# MSSRP-Connectors.net
KiCad netlist of a schematic drawn in EAGLE
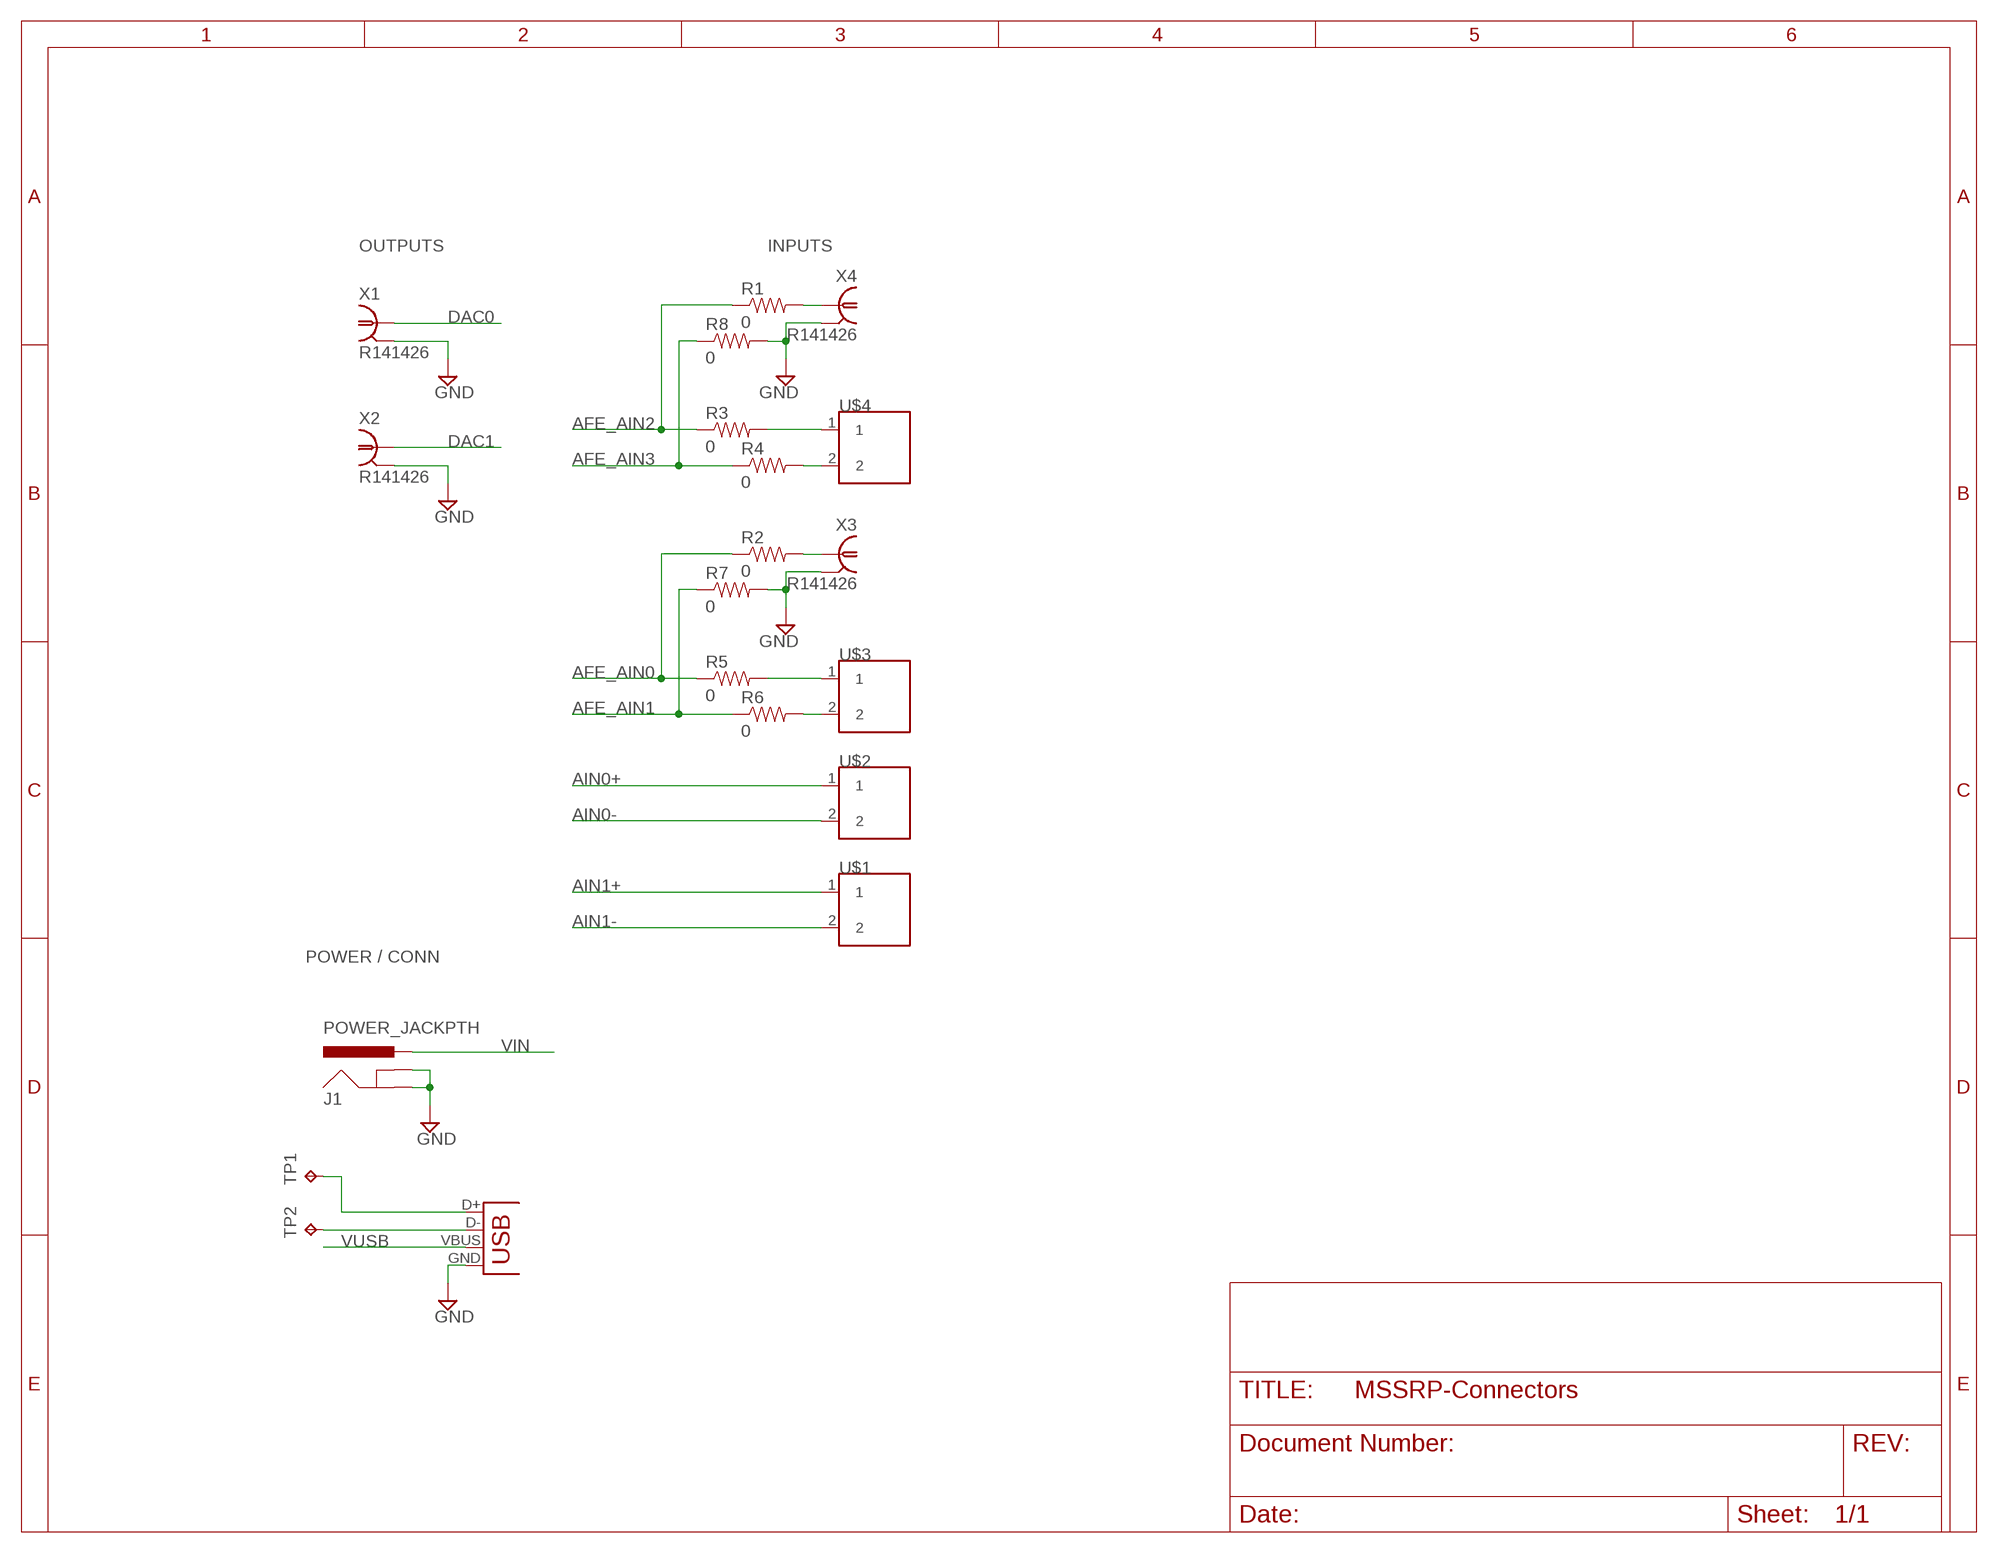
[diagram p0: schematic, sheet 1]

(export (version "E")
  (design (tool "Eeschema 10.0.6"))
  (components
    (comp (ref "J1")
      (value "POWER_JACKPTH")
      (footprint "eagle-import:POWER_JACK_PTH")
      (libsource (lib "eagle-import") (part "POWER_JACKPTH"))
    )
    (comp (ref "JP1")
      (value "USBSMD")
      (footprint "eagle-import:USB-MINIB")
      (libsource (lib "eagle-import") (part "USBSMD"))
    )
    (comp (ref "R1")
      (value "0")
      (footprint "eagle-import:0603")
      (libsource (lib "eagle-import") (part "0OHM1/10W5%(0603)"))
    )
    (comp (ref "R2")
      (value "0")
      (footprint "eagle-import:0603")
      (libsource (lib "eagle-import") (part "0OHM1/10W5%(0603)"))
    )
    (comp (ref "R3")
      (value "0")
      (footprint "eagle-import:0603")
      (libsource (lib "eagle-import") (part "0OHM1/10W5%(0603)"))
    )
    (comp (ref "R4")
      (value "0")
      (footprint "eagle-import:0603")
      (libsource (lib "eagle-import") (part "0OHM1/10W5%(0603)"))
    )
    (comp (ref "R5")
      (value "0")
      (footprint "eagle-import:0603")
      (libsource (lib "eagle-import") (part "0OHM1/10W5%(0603)"))
    )
    (comp (ref "R6")
      (value "0")
      (footprint "eagle-import:0603")
      (libsource (lib "eagle-import") (part "0OHM1/10W5%(0603)"))
    )
    (comp (ref "R7")
      (value "0")
      (footprint "eagle-import:0603")
      (libsource (lib "eagle-import") (part "0OHM1/10W5%(0603)"))
    )
    (comp (ref "R8")
      (value "0")
      (footprint "eagle-import:0603")
      (libsource (lib "eagle-import") (part "0OHM1/10W5%(0603)"))
    )
    (comp (ref "TP1")
      (value "TPPAD1-13")
      (footprint "eagle-import:P1-13")
      (libsource (lib "eagle-import") (part "TPPAD1-13"))
    )
    (comp (ref "TP2")
      (value "TPPAD1-13")
      (footprint "eagle-import:P1-13")
      (libsource (lib "eagle-import") (part "TPPAD1-13"))
    )
    (comp (ref "U$1")
      (value "TE-2-TERMBLOCK")
      (footprint "eagle-import:TE-2-TERMBLOCK")
      (libsource (lib "eagle-import") (part "TE-2-TERMBLOCK"))
    )
    (comp (ref "U$2")
      (value "TE-2-TERMBLOCK")
      (footprint "eagle-import:TE-2-TERMBLOCK")
      (libsource (lib "eagle-import") (part "TE-2-TERMBLOCK"))
    )
    (comp (ref "U$3")
      (value "TE-2-TERMBLOCK")
      (footprint "eagle-import:TE-2-TERMBLOCK")
      (libsource (lib "eagle-import") (part "TE-2-TERMBLOCK"))
    )
    (comp (ref "U$4")
      (value "TE-2-TERMBLOCK")
      (footprint "eagle-import:TE-2-TERMBLOCK")
      (libsource (lib "eagle-import") (part "TE-2-TERMBLOCK"))
    )
    (comp (ref "X1")
      (value "R141426")
      (footprint "eagle-import:R141426")
      (fields (field (name "MF") "FARNELL") (field (name "MPN") "R141426161"))
      (libsource (lib "eagle-import") (part "R141426"))
    )
    (comp (ref "X2")
      (value "R141426")
      (footprint "eagle-import:R141426")
      (fields (field (name "MF") "FARNELL") (field (name "MPN") "R141426161"))
      (libsource (lib "eagle-import") (part "R141426"))
    )
    (comp (ref "X3")
      (value "R141426")
      (footprint "eagle-import:R141426")
      (fields (field (name "MF") "FARNELL") (field (name "MPN") "R141426161"))
      (libsource (lib "eagle-import") (part "R141426"))
    )
    (comp (ref "X4")
      (value "R141426")
      (footprint "eagle-import:R141426")
      (fields (field (name "MF") "FARNELL") (field (name "MPN") "R141426161"))
      (libsource (lib "eagle-import") (part "R141426"))
    )
  )
  (nets
    (net (code "1") (name "/AFE_AIN0") (class "Default")
      (node (ref "R2") (pin "1") (pinfunction "1_1") (pintype "passive"))
      (node (ref "R5") (pin "1") (pinfunction "1_1") (pintype "passive"))
    )
    (net (code "2") (name "/AFE_AIN1") (class "Default")
      (node (ref "R6") (pin "1") (pinfunction "1_1") (pintype "passive"))
      (node (ref "R7") (pin "1") (pinfunction "1_1") (pintype "passive"))
    )
    (net (code "3") (name "/AFE_AIN2") (class "Default")
      (node (ref "R1") (pin "1") (pinfunction "1_1") (pintype "passive"))
      (node (ref "R3") (pin "1") (pinfunction "1_1") (pintype "passive"))
    )
    (net (code "4") (name "/AFE_AIN3") (class "Default")
      (node (ref "R4") (pin "1") (pinfunction "1_1") (pintype "passive"))
      (node (ref "R8") (pin "1") (pinfunction "1_1") (pintype "passive"))
    )
    (net (code "5") (name "/AIN0+") (class "Default")
      (node (ref "U$2") (pin "1") (pinfunction "1_1") (pintype "passive"))
    )
    (net (code "6") (name "/AIN0-") (class "Default")
      (node (ref "U$2") (pin "2") (pinfunction "2_2") (pintype "passive"))
    )
    (net (code "7") (name "/AIN1+") (class "Default")
      (node (ref "U$1") (pin "1") (pinfunction "1_1") (pintype "passive"))
    )
    (net (code "8") (name "/AIN1-") (class "Default")
      (node (ref "U$1") (pin "2") (pinfunction "2_2") (pintype "passive"))
    )
    (net (code "9") (name "/DAC0") (class "Default")
      (node (ref "X1") (pin "1") (pinfunction "1_1") (pintype "passive"))
    )
    (net (code "10") (name "/DAC1") (class "Default")
      (node (ref "X2") (pin "1") (pinfunction "1_1") (pintype "passive"))
    )
    (net (code "11") (name "/VIN") (class "Default")
      (node (ref "J1") (pin "PWR") (pinfunction "PWR_PWR") (pintype "bidirectional"))
    )
    (net (code "12") (name "/VUSB") (class "Default")
      (node (ref "JP1") (pin "VBUS") (pinfunction "VBUS_VBUS") (pintype "bidirectional"))
    )
    (net (code "13") (name "GND") (class "Default")
      (node (ref "J1") (pin "GND") (pinfunction "GND_GND") (pintype "bidirectional"))
      (node (ref "J1") (pin "GNDBREAK") (pinfunction "GNDBREAK_GNDBREAK") (pintype "bidirectional"))
      (node (ref "JP1") (pin "GND") (pinfunction "GND_GND") (pintype "bidirectional"))
      (node (ref "R7") (pin "2") (pinfunction "2_2") (pintype "passive"))
      (node (ref "R8") (pin "2") (pinfunction "2_2") (pintype "passive"))
      (node (ref "X1") (pin "2") (pinfunction "2_2") (pintype "passive"))
      (node (ref "X1") (pin "3") (pinfunction "2_3") (pintype "passive"))
      (node (ref "X1") (pin "4") (pinfunction "2_4") (pintype "passive"))
      (node (ref "X1") (pin "5") (pinfunction "2_5") (pintype "passive"))
      (node (ref "X2") (pin "2") (pinfunction "2_2") (pintype "passive"))
      (node (ref "X2") (pin "3") (pinfunction "2_3") (pintype "passive"))
      (node (ref "X2") (pin "4") (pinfunction "2_4") (pintype "passive"))
      (node (ref "X2") (pin "5") (pinfunction "2_5") (pintype "passive"))
      (node (ref "X3") (pin "2") (pinfunction "2_2") (pintype "passive"))
      (node (ref "X3") (pin "3") (pinfunction "2_3") (pintype "passive"))
      (node (ref "X3") (pin "4") (pinfunction "2_4") (pintype "passive"))
      (node (ref "X3") (pin "5") (pinfunction "2_5") (pintype "passive"))
      (node (ref "X4") (pin "2") (pinfunction "2_2") (pintype "passive"))
      (node (ref "X4") (pin "3") (pinfunction "2_3") (pintype "passive"))
      (node (ref "X4") (pin "4") (pinfunction "2_4") (pintype "passive"))
      (node (ref "X4") (pin "5") (pinfunction "2_5") (pintype "passive"))
    )
    (net (code "14") (name "Net-(JP1-PadD+)") (class "Default")
      (node (ref "JP1") (pin "D+") (pinfunction "D+_D+") (pintype "bidirectional"))
      (node (ref "TP1") (pin "TP") (pinfunction "TP_TP") (pintype "input"))
    )
    (net (code "15") (name "Net-(JP1-PadD-)") (class "Default")
      (node (ref "JP1") (pin "D-") (pinfunction "D-_D-") (pintype "bidirectional"))
      (node (ref "TP2") (pin "TP") (pinfunction "TP_TP") (pintype "input"))
    )
    (net (code "16") (name "Net-(R1-Pad2)") (class "Default")
      (node (ref "R1") (pin "2") (pinfunction "2_2") (pintype "passive"))
      (node (ref "X4") (pin "1") (pinfunction "1_1") (pintype "passive"))
    )
    (net (code "17") (name "Net-(R2-Pad2)") (class "Default")
      (node (ref "R2") (pin "2") (pinfunction "2_2") (pintype "passive"))
      (node (ref "X3") (pin "1") (pinfunction "1_1") (pintype "passive"))
    )
    (net (code "18") (name "Net-(R3-Pad2)") (class "Default")
      (node (ref "R3") (pin "2") (pinfunction "2_2") (pintype "passive"))
      (node (ref "U$4") (pin "1") (pinfunction "1_1") (pintype "passive"))
    )
    (net (code "19") (name "Net-(R4-Pad2)") (class "Default")
      (node (ref "R4") (pin "2") (pinfunction "2_2") (pintype "passive"))
      (node (ref "U$4") (pin "2") (pinfunction "2_2") (pintype "passive"))
    )
    (net (code "20") (name "Net-(R5-Pad2)") (class "Default")
      (node (ref "R5") (pin "2") (pinfunction "2_2") (pintype "passive"))
      (node (ref "U$3") (pin "1") (pinfunction "1_1") (pintype "passive"))
    )
    (net (code "21") (name "Net-(R6-Pad2)") (class "Default")
      (node (ref "R6") (pin "2") (pinfunction "2_2") (pintype "passive"))
      (node (ref "U$3") (pin "2") (pinfunction "2_2") (pintype "passive"))
    )
  )
)
